# OMAPL-Extrention_Prototype.net
KiCad netlist of a schematic drawn in Altium Designer
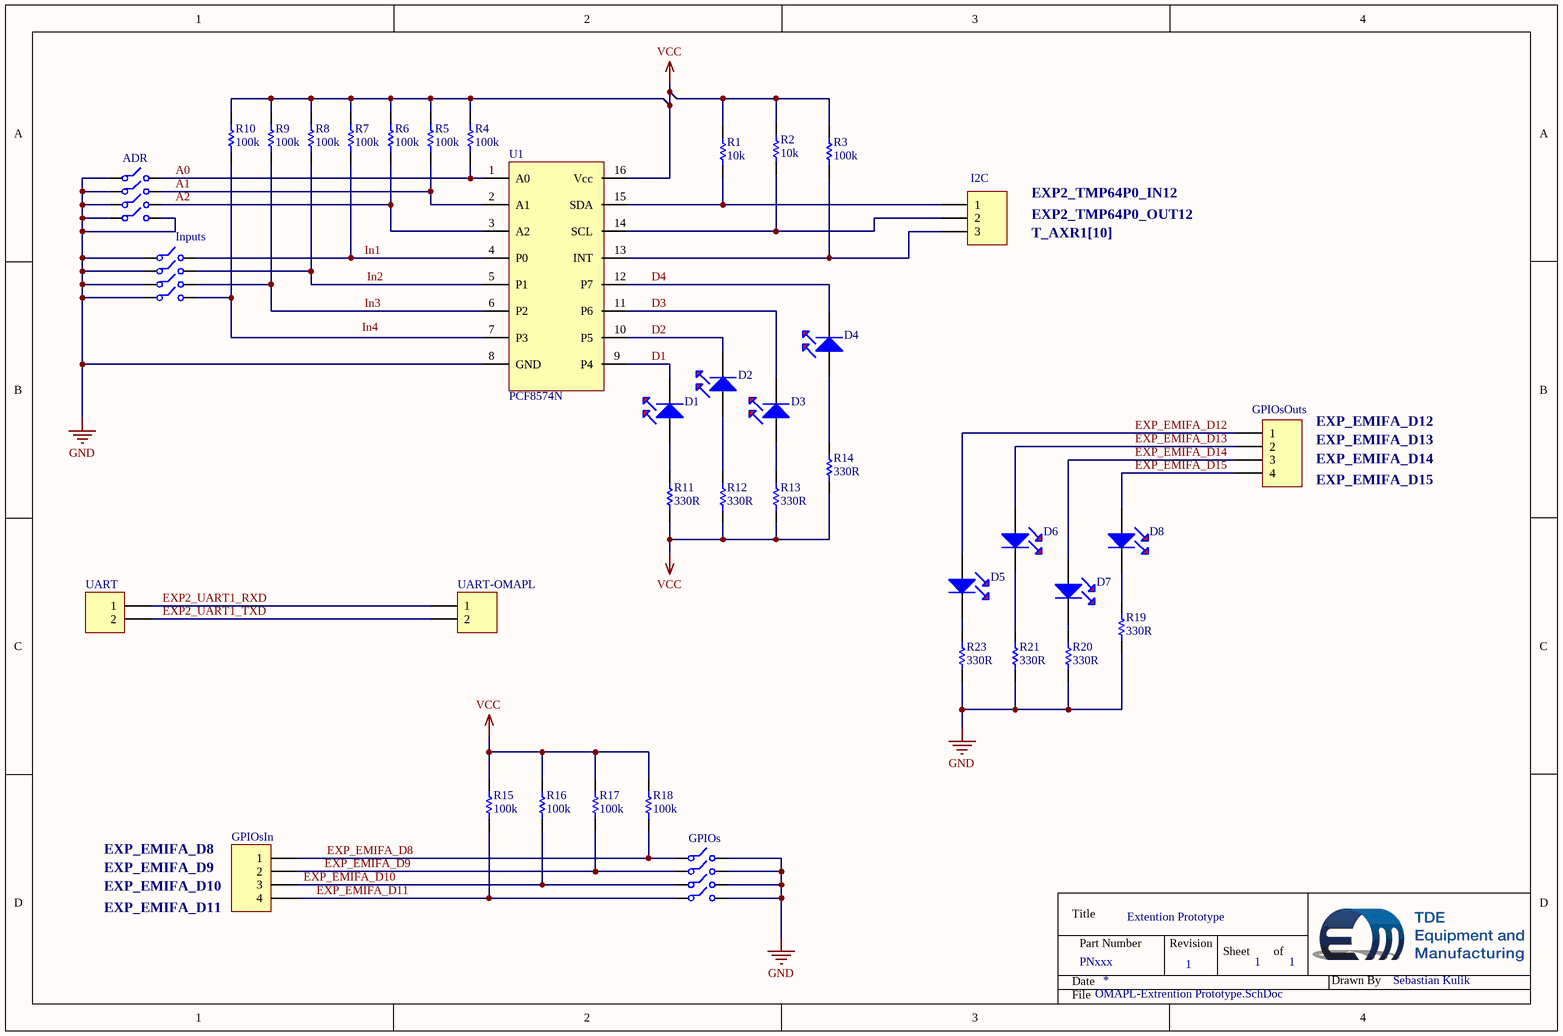
[diagram p0: OMAPL-Extrention Prototype.SchDoc]

(export (version "E")
  (design (tool "Eeschema 10.0.6"))
  (components
    (comp (ref "ADR")
      (value "WS-DITV-4DIP")
      (footprint "DIP-8-Ceramic-HT")
      (description "4 way DIP switch")
      (fields (field (name "MANUFACTURER") "WE") (field (name "PUBLISHER") "Sebastian Kulik"))
      (libsource (lib "Mechanical") (part "WS-DITV-4DIP"))
    )
    (comp (ref "D1")
      (value "151051RS11000")
      (footprint "LED2X5")
      (description "LED, 5mm, red, THT")
      (fields (field (name "MANUFACTURER") "WE") (field (name "PUBLISHER") "Sebastian Kulik"))
      (libsource (lib "Discrete") (part "151051RS11000"))
    )
    (comp (ref "D2")
      (value "151051RS11000")
      (footprint "LED2X5")
      (description "LED, 5mm, red, THT")
      (fields (field (name "MANUFACTURER") "WE") (field (name "PUBLISHER") "Sebastian Kulik"))
      (libsource (lib "Discrete") (part "151051RS11000"))
    )
    (comp (ref "D3")
      (value "151051RS11000")
      (footprint "LED2X5")
      (description "LED, 5mm, red, THT")
      (fields (field (name "MANUFACTURER") "WE") (field (name "PUBLISHER") "Sebastian Kulik"))
      (libsource (lib "Discrete") (part "151051RS11000"))
    )
    (comp (ref "D4")
      (value "151051RS11000")
      (footprint "LED2X5")
      (description "LED, 5mm, red, THT")
      (fields (field (name "MANUFACTURER") "WE") (field (name "PUBLISHER") "Sebastian Kulik"))
      (libsource (lib "Discrete") (part "151051RS11000"))
    )
    (comp (ref "D5")
      (value "151051RS11000")
      (footprint "LED2X5")
      (description "LED, 5mm, red, THT")
      (fields (field (name "MANUFACTURER") "WE") (field (name "PUBLISHER") "Sebastian Kulik"))
      (libsource (lib "Discrete") (part "151051RS11000"))
    )
    (comp (ref "D6")
      (value "151051RS11000")
      (footprint "LED2X5")
      (description "LED, 5mm, red, THT")
      (fields (field (name "MANUFACTURER") "WE") (field (name "PUBLISHER") "Sebastian Kulik"))
      (libsource (lib "Discrete") (part "151051RS11000"))
    )
    (comp (ref "D7")
      (value "151051RS11000")
      (footprint "LED2X5")
      (description "LED, 5mm, red, THT")
      (fields (field (name "MANUFACTURER") "WE") (field (name "PUBLISHER") "Sebastian Kulik"))
      (libsource (lib "Discrete") (part "151051RS11000"))
    )
    (comp (ref "D8")
      (value "151051RS11000")
      (footprint "LED2X5")
      (description "LED, 5mm, red, THT")
      (fields (field (name "MANUFACTURER") "WE") (field (name "PUBLISHER") "Sebastian Kulik"))
      (libsource (lib "Discrete") (part "151051RS11000"))
    )
    (comp (ref "GPIOs")
      (value "WS-DITV-4DIP")
      (footprint "DIP-8-Ceramic-HT")
      (description "4 way DIP switch")
      (fields (field (name "MANUFACTURER") "WE") (field (name "PUBLISHER") "Sebastian Kulik"))
      (libsource (lib "Mechanical") (part "WS-DITV-4DIP"))
    )
    (comp (ref "GPIOsIn")
      (value "Plug_4_90_2.54")
      (footprint "HDR1X4")
      (description "Plug, 4-Pin")
      (fields (field (name "MANUFACTURER") "WE") (field (name "PUBLISHER") "Sebastian Kulik"))
      (libsource (lib "") (part "Plug_4_90_2.54_1"))
    )
    (comp (ref "GPIOsOuts")
      (value "Plug_4_90_2.54")
      (footprint "HDR1X4")
      (description "Plug, 4-Pin")
      (fields (field (name "MANUFACTURER") "WE") (field (name "PUBLISHER") "Sebastian Kulik"))
      (libsource (lib "Connectors") (part "Plug_4_90_2.54"))
    )
    (comp (ref "I2C")
      (value "Plug_3_90_2.54")
      (footprint "HDR1X3")
      (description "Plug,-3-Pin")
      (fields (field (name "MANUFACTURER") "WE") (field (name "PUBLISHER") "Sebastian Kulik"))
      (libsource (lib "Connectors") (part "Plug_3_90_2.54"))
    )
    (comp (ref "Inputs")
      (value "WS-DITV-4DIP")
      (footprint "DIP-8-Ceramic-HT")
      (description "4 way DIP switch")
      (fields (field (name "MANUFACTURER") "WE") (field (name "PUBLISHER") "Sebastian Kulik"))
      (libsource (lib "Mechanical") (part "WS-DITV-4DIP"))
    )
    (comp (ref "R1")
      (value "10k")
      (footprint "Dummy-10mm")
      (description "Resistor-Dummy-THT")
      (fields (field (name "PUBLISHER") "Sebastian Kulik"))
      (libsource (lib "Resistors") (part "Resistor-Dummy-THT"))
    )
    (comp (ref "R2")
      (value "10k")
      (footprint "Dummy-10mm")
      (description "Resistor-Dummy-THT")
      (fields (field (name "PUBLISHER") "Sebastian Kulik"))
      (libsource (lib "Resistors") (part "Resistor-Dummy-THT"))
    )
    (comp (ref "R3")
      (value "100k")
      (footprint "Dummy-10mm")
      (description "Resistor-Dummy-THT")
      (fields (field (name "PUBLISHER") "Sebastian Kulik"))
      (libsource (lib "Resistors") (part "Resistor-Dummy-THT"))
    )
    (comp (ref "R4")
      (value "100k")
      (footprint "Dummy-10mm")
      (description "Resistor-Dummy-THT")
      (fields (field (name "PUBLISHER") "Sebastian Kulik"))
      (libsource (lib "Resistors") (part "Resistor-Dummy-THT"))
    )
    (comp (ref "R5")
      (value "100k")
      (footprint "Dummy-10mm")
      (description "Resistor-Dummy-THT")
      (fields (field (name "PUBLISHER") "Sebastian Kulik"))
      (libsource (lib "Resistors") (part "Resistor-Dummy-THT"))
    )
    (comp (ref "R6")
      (value "100k")
      (footprint "Dummy-10mm")
      (description "Resistor-Dummy-THT")
      (fields (field (name "PUBLISHER") "Sebastian Kulik"))
      (libsource (lib "Resistors") (part "Resistor-Dummy-THT"))
    )
    (comp (ref "R7")
      (value "100k")
      (footprint "Dummy-10mm")
      (description "Resistor-Dummy-THT")
      (fields (field (name "PUBLISHER") "Sebastian Kulik"))
      (libsource (lib "Resistors") (part "Resistor-Dummy-THT"))
    )
    (comp (ref "R8")
      (value "100k")
      (footprint "Dummy-10mm")
      (description "Resistor-Dummy-THT")
      (fields (field (name "PUBLISHER") "Sebastian Kulik"))
      (libsource (lib "Resistors") (part "Resistor-Dummy-THT"))
    )
    (comp (ref "R9")
      (value "100k")
      (footprint "Dummy-10mm")
      (description "Resistor-Dummy-THT")
      (fields (field (name "PUBLISHER") "Sebastian Kulik"))
      (libsource (lib "Resistors") (part "Resistor-Dummy-THT"))
    )
    (comp (ref "R10")
      (value "100k")
      (footprint "Dummy-10mm")
      (description "Resistor-Dummy-THT")
      (fields (field (name "PUBLISHER") "Sebastian Kulik"))
      (libsource (lib "Resistors") (part "Resistor-Dummy-THT"))
    )
    (comp (ref "R11")
      (value "330R")
      (footprint "Dummy-10mm")
      (description "Resistor-Dummy-THT")
      (fields (field (name "PUBLISHER") "Sebastian Kulik"))
      (libsource (lib "Resistors") (part "Resistor-Dummy-THT"))
    )
    (comp (ref "R12")
      (value "330R")
      (footprint "Dummy-10mm")
      (description "Resistor-Dummy-THT")
      (fields (field (name "PUBLISHER") "Sebastian Kulik"))
      (libsource (lib "Resistors") (part "Resistor-Dummy-THT"))
    )
    (comp (ref "R13")
      (value "330R")
      (footprint "Dummy-10mm")
      (description "Resistor-Dummy-THT")
      (fields (field (name "PUBLISHER") "Sebastian Kulik"))
      (libsource (lib "Resistors") (part "Resistor-Dummy-THT"))
    )
    (comp (ref "R14")
      (value "330R")
      (footprint "Dummy-10mm")
      (description "Resistor-Dummy-THT")
      (fields (field (name "PUBLISHER") "Sebastian Kulik"))
      (libsource (lib "Resistors") (part "Resistor-Dummy-THT"))
    )
    (comp (ref "R15")
      (value "100k")
      (footprint "Dummy-10mm")
      (description "Resistor-Dummy-THT")
      (fields (field (name "PUBLISHER") "Sebastian Kulik"))
      (libsource (lib "Resistors") (part "Resistor-Dummy-THT"))
    )
    (comp (ref "R16")
      (value "100k")
      (footprint "Dummy-10mm")
      (description "Resistor-Dummy-THT")
      (fields (field (name "PUBLISHER") "Sebastian Kulik"))
      (libsource (lib "Resistors") (part "Resistor-Dummy-THT"))
    )
    (comp (ref "R17")
      (value "100k")
      (footprint "Dummy-10mm")
      (description "Resistor-Dummy-THT")
      (fields (field (name "PUBLISHER") "Sebastian Kulik"))
      (libsource (lib "Resistors") (part "Resistor-Dummy-THT"))
    )
    (comp (ref "R18")
      (value "100k")
      (footprint "Dummy-10mm")
      (description "Resistor-Dummy-THT")
      (fields (field (name "PUBLISHER") "Sebastian Kulik"))
      (libsource (lib "Resistors") (part "Resistor-Dummy-THT"))
    )
    (comp (ref "R19")
      (value "330R")
      (footprint "Dummy-10mm")
      (description "Resistor-Dummy-THT")
      (fields (field (name "PUBLISHER") "Sebastian Kulik"))
      (libsource (lib "Resistors") (part "Resistor-Dummy-THT"))
    )
    (comp (ref "R20")
      (value "330R")
      (footprint "Dummy-10mm")
      (description "Resistor-Dummy-THT")
      (fields (field (name "PUBLISHER") "Sebastian Kulik"))
      (libsource (lib "Resistors") (part "Resistor-Dummy-THT"))
    )
    (comp (ref "R21")
      (value "330R")
      (footprint "Dummy-10mm")
      (description "Resistor-Dummy-THT")
      (fields (field (name "PUBLISHER") "Sebastian Kulik"))
      (libsource (lib "Resistors") (part "Resistor-Dummy-THT"))
    )
    (comp (ref "R23")
      (value "330R")
      (footprint "Dummy-10mm")
      (description "Resistor-Dummy-THT")
      (fields (field (name "PUBLISHER") "Sebastian Kulik"))
      (libsource (lib "Resistors") (part "Resistor-Dummy-THT"))
    )
    (comp (ref "U1")
      (value "PCF8574N")
      (footprint "DIP-16")
      (description "I2C 8-bit expander")
      (fields (field (name "MANUFACTURER") "TI") (field (name "PUBLISHER") "Sebastian Kulik"))
      (libsource (lib "ICs") (part "PCF8574N"))
    )
    (comp (ref "UART")
      (value "Plug_2_90_2.54")
      (footprint "HDR1X2")
      (description "Plug, 2-Pin")
      (fields (field (name "MANUFACTURER") "WE") (field (name "PUBLISHER") "Sebastian Kulik"))
      (libsource (lib "") (part "Plug_2_90_2.54_1"))
    )
    (comp (ref "UART-OMAPL")
      (value "Plug_2_90_2.54")
      (footprint "HDR1X2")
      (description "Plug, 2-Pin")
      (fields (field (name "MANUFACTURER") "WE") (field (name "PUBLISHER") "Sebastian Kulik"))
      (libsource (lib "Connectors") (part "Plug_2_90_2.54"))
    )
  )
  (nets
    (net (code "1") (name "/A0") (class "Default")
      (node (ref "ADR") (pin "8") (pinfunction "8_8") (pintype "passive"))
      (node (ref "R4") (pin "1") (pinfunction "1_1") (pintype "passive"))
      (node (ref "U1") (pin "1") (pinfunction "A0_1") (pintype "passive"))
    )
    (net (code "2") (name "/A1") (class "Default")
      (node (ref "ADR") (pin "7") (pinfunction "7_7") (pintype "passive"))
      (node (ref "R5") (pin "1") (pinfunction "1_1") (pintype "passive"))
      (node (ref "U1") (pin "2") (pinfunction "A1_2") (pintype "passive"))
    )
    (net (code "3") (name "/A2") (class "Default")
      (node (ref "ADR") (pin "6") (pinfunction "6_6") (pintype "passive"))
      (node (ref "R6") (pin "1") (pinfunction "1_1") (pintype "passive"))
      (node (ref "U1") (pin "3") (pinfunction "A2_3") (pintype "passive"))
    )
    (net (code "4") (name "/D1") (class "Default")
      (node (ref "D1") (pin "K") (pinfunction "K_K") (pintype "passive"))
      (node (ref "U1") (pin "9") (pinfunction "P4_9") (pintype "power_in"))
    )
    (net (code "5") (name "/D2") (class "Default")
      (node (ref "D2") (pin "K") (pinfunction "K_K") (pintype "passive"))
      (node (ref "U1") (pin "10") (pinfunction "P5_10") (pintype "power_in"))
    )
    (net (code "6") (name "/D3") (class "Default")
      (node (ref "D3") (pin "K") (pinfunction "K_K") (pintype "passive"))
      (node (ref "U1") (pin "11") (pinfunction "P6_11") (pintype "power_in"))
    )
    (net (code "7") (name "/D4") (class "Default")
      (node (ref "D4") (pin "K") (pinfunction "K_K") (pintype "passive"))
      (node (ref "U1") (pin "12") (pinfunction "P7_12") (pintype "power_in"))
    )
    (net (code "8") (name "/EXP2_UART1_RXD") (class "Default")
      (node (ref "UART") (pin "1") (pinfunction "1_1") (pintype "passive"))
      (node (ref "UART-OMAPL") (pin "1") (pinfunction "1_1") (pintype "passive"))
    )
    (net (code "9") (name "/EXP2_UART1_TXD") (class "Default")
      (node (ref "UART") (pin "2") (pinfunction "2_2") (pintype "passive"))
      (node (ref "UART-OMAPL") (pin "2") (pinfunction "2_2") (pintype "passive"))
    )
    (net (code "10") (name "/EXP_EMIFA_D8") (class "Default")
      (node (ref "GPIOs") (pin "1") (pinfunction "1_1") (pintype "passive"))
      (node (ref "GPIOsIn") (pin "1") (pinfunction "1_1") (pintype "passive"))
      (node (ref "R18") (pin "1") (pinfunction "1_1") (pintype "passive"))
    )
    (net (code "11") (name "/EXP_EMIFA_D9") (class "Default")
      (node (ref "GPIOs") (pin "2") (pinfunction "2_2") (pintype "passive"))
      (node (ref "GPIOsIn") (pin "2") (pinfunction "2_2") (pintype "passive"))
      (node (ref "R17") (pin "1") (pinfunction "1_1") (pintype "passive"))
    )
    (net (code "12") (name "/EXP_EMIFA_D10") (class "Default")
      (node (ref "GPIOs") (pin "3") (pinfunction "3_3") (pintype "passive"))
      (node (ref "GPIOsIn") (pin "3") (pinfunction "3_3") (pintype "passive"))
      (node (ref "R16") (pin "1") (pinfunction "1_1") (pintype "passive"))
    )
    (net (code "13") (name "/EXP_EMIFA_D11") (class "Default")
      (node (ref "GPIOs") (pin "4") (pinfunction "4_4") (pintype "passive"))
      (node (ref "GPIOsIn") (pin "4") (pinfunction "4_4") (pintype "passive"))
      (node (ref "R15") (pin "1") (pinfunction "1_1") (pintype "passive"))
    )
    (net (code "14") (name "/EXP_EMIFA_D12") (class "Default")
      (node (ref "D5") (pin "A") (pinfunction "A_A") (pintype "passive"))
      (node (ref "GPIOsOuts") (pin "1") (pinfunction "1_1") (pintype "passive"))
    )
    (net (code "15") (name "/EXP_EMIFA_D13") (class "Default")
      (node (ref "D6") (pin "A") (pinfunction "A_A") (pintype "passive"))
      (node (ref "GPIOsOuts") (pin "2") (pinfunction "2_2") (pintype "passive"))
    )
    (net (code "16") (name "/EXP_EMIFA_D14") (class "Default")
      (node (ref "D7") (pin "A") (pinfunction "A_A") (pintype "passive"))
      (node (ref "GPIOsOuts") (pin "3") (pinfunction "3_3") (pintype "passive"))
    )
    (net (code "17") (name "/EXP_EMIFA_D15") (class "Default")
      (node (ref "D8") (pin "A") (pinfunction "A_A") (pintype "passive"))
      (node (ref "GPIOsOuts") (pin "4") (pinfunction "4_4") (pintype "passive"))
    )
    (net (code "18") (name "/In1") (class "Default")
      (node (ref "Inputs") (pin "8") (pinfunction "8_8") (pintype "passive"))
      (node (ref "R7") (pin "1") (pinfunction "1_1") (pintype "passive"))
      (node (ref "U1") (pin "4") (pinfunction "P0_4") (pintype "passive"))
    )
    (net (code "19") (name "/In2") (class "Default")
      (node (ref "Inputs") (pin "7") (pinfunction "7_7") (pintype "passive"))
      (node (ref "R8") (pin "1") (pinfunction "1_1") (pintype "passive"))
      (node (ref "U1") (pin "5") (pinfunction "P1_5") (pintype "passive"))
    )
    (net (code "20") (name "/In3") (class "Default")
      (node (ref "Inputs") (pin "6") (pinfunction "6_6") (pintype "passive"))
      (node (ref "R9") (pin "1") (pinfunction "1_1") (pintype "passive"))
      (node (ref "U1") (pin "6") (pinfunction "P2_6") (pintype "passive"))
    )
    (net (code "22") (name "GND") (class "Default")
      (node (ref "ADR") (pin "1") (pinfunction "1_1") (pintype "passive"))
      (node (ref "ADR") (pin "2") (pinfunction "2_2") (pintype "passive"))
      (node (ref "ADR") (pin "3") (pinfunction "3_3") (pintype "passive"))
      (node (ref "ADR") (pin "4") (pinfunction "4_4") (pintype "passive"))
      (node (ref "ADR") (pin "5") (pinfunction "5_5") (pintype "passive"))
      (node (ref "GPIOs") (pin "5") (pinfunction "5_5") (pintype "passive"))
      (node (ref "GPIOs") (pin "6") (pinfunction "6_6") (pintype "passive"))
      (node (ref "GPIOs") (pin "7") (pinfunction "7_7") (pintype "passive"))
      (node (ref "GPIOs") (pin "8") (pinfunction "8_8") (pintype "passive"))
      (node (ref "Inputs") (pin "1") (pinfunction "1_1") (pintype "passive"))
      (node (ref "Inputs") (pin "2") (pinfunction "2_2") (pintype "passive"))
      (node (ref "Inputs") (pin "3") (pinfunction "3_3") (pintype "passive"))
      (node (ref "Inputs") (pin "4") (pinfunction "4_4") (pintype "passive"))
      (node (ref "R19") (pin "1") (pinfunction "1_1") (pintype "passive"))
      (node (ref "R20") (pin "1") (pinfunction "1_1") (pintype "passive"))
      (node (ref "R21") (pin "1") (pinfunction "1_1") (pintype "passive"))
      (node (ref "R23") (pin "1") (pinfunction "1_1") (pintype "passive"))
      (node (ref "U1") (pin "8") (pinfunction "GND_8") (pintype "power_in"))
    )
    (net (code "23") (name "Net-(D1-PadA)") (class "Default")
      (node (ref "D1") (pin "A") (pinfunction "A_A") (pintype "passive"))
      (node (ref "R11") (pin "2") (pinfunction "2_2") (pintype "passive"))
    )
    (net (code "24") (name "Net-(D2-PadA)") (class "Default")
      (node (ref "D2") (pin "A") (pinfunction "A_A") (pintype "passive"))
      (node (ref "R12") (pin "2") (pinfunction "2_2") (pintype "passive"))
    )
    (net (code "25") (name "Net-(D3-PadA)") (class "Default")
      (node (ref "D3") (pin "A") (pinfunction "A_A") (pintype "passive"))
      (node (ref "R13") (pin "2") (pinfunction "2_2") (pintype "passive"))
    )
    (net (code "26") (name "Net-(D4-PadA)") (class "Default")
      (node (ref "D4") (pin "A") (pinfunction "A_A") (pintype "passive"))
      (node (ref "R14") (pin "2") (pinfunction "2_2") (pintype "passive"))
    )
    (net (code "27") (name "Net-(D5-PadK)") (class "Default")
      (node (ref "D5") (pin "K") (pinfunction "K_K") (pintype "passive"))
      (node (ref "R23") (pin "2") (pinfunction "2_2") (pintype "passive"))
    )
    (net (code "28") (name "Net-(D6-PadK)") (class "Default")
      (node (ref "D6") (pin "K") (pinfunction "K_K") (pintype "passive"))
      (node (ref "R21") (pin "2") (pinfunction "2_2") (pintype "passive"))
    )
    (net (code "29") (name "Net-(D7-PadK)") (class "Default")
      (node (ref "D7") (pin "K") (pinfunction "K_K") (pintype "passive"))
      (node (ref "R20") (pin "2") (pinfunction "2_2") (pintype "passive"))
    )
    (net (code "30") (name "Net-(D8-PadK)") (class "Default")
      (node (ref "D8") (pin "K") (pinfunction "K_K") (pintype "passive"))
      (node (ref "R19") (pin "2") (pinfunction "2_2") (pintype "passive"))
    )
    (net (code "31") (name "Net-(U1-INT)") (class "Default")
      (node (ref "I2C") (pin "3") (pinfunction "3_3") (pintype "passive"))
      (node (ref "R3") (pin "1") (pinfunction "1_1") (pintype "passive"))
      (node (ref "U1") (pin "13") (pinfunction "INT_13") (pintype "passive"))
    )
    (net (code "32") (name "Net-(U1-P3)") (class "Default")
      (node (ref "Inputs") (pin "5") (pinfunction "5_5") (pintype "passive"))
      (node (ref "R10") (pin "1") (pinfunction "1_1") (pintype "passive"))
      (node (ref "U1") (pin "7") (pinfunction "P3_7") (pintype "passive"))
    )
    (net (code "33") (name "Net-(U1-SCL)") (class "Default")
      (node (ref "I2C") (pin "2") (pinfunction "2_2") (pintype "passive"))
      (node (ref "R2") (pin "1") (pinfunction "1_1") (pintype "passive"))
      (node (ref "U1") (pin "14") (pinfunction "SCL_14") (pintype "passive"))
    )
    (net (code "34") (name "Net-(U1-SDA)") (class "Default")
      (node (ref "I2C") (pin "1") (pinfunction "1_1") (pintype "passive"))
      (node (ref "R1") (pin "1") (pinfunction "1_1") (pintype "passive"))
      (node (ref "U1") (pin "15") (pinfunction "SDA_15") (pintype "power_in"))
    )
    (net (code "35") (name "VCC") (class "Default")
      (node (ref "R1") (pin "2") (pinfunction "2_2") (pintype "passive"))
      (node (ref "R10") (pin "2") (pinfunction "2_2") (pintype "passive"))
      (node (ref "R11") (pin "1") (pinfunction "1_1") (pintype "passive"))
      (node (ref "R12") (pin "1") (pinfunction "1_1") (pintype "passive"))
      (node (ref "R13") (pin "1") (pinfunction "1_1") (pintype "passive"))
      (node (ref "R14") (pin "1") (pinfunction "1_1") (pintype "passive"))
      (node (ref "R15") (pin "2") (pinfunction "2_2") (pintype "passive"))
      (node (ref "R16") (pin "2") (pinfunction "2_2") (pintype "passive"))
      (node (ref "R17") (pin "2") (pinfunction "2_2") (pintype "passive"))
      (node (ref "R18") (pin "2") (pinfunction "2_2") (pintype "passive"))
      (node (ref "R2") (pin "2") (pinfunction "2_2") (pintype "passive"))
      (node (ref "R3") (pin "2") (pinfunction "2_2") (pintype "passive"))
      (node (ref "R4") (pin "2") (pinfunction "2_2") (pintype "passive"))
      (node (ref "R5") (pin "2") (pinfunction "2_2") (pintype "passive"))
      (node (ref "R6") (pin "2") (pinfunction "2_2") (pintype "passive"))
      (node (ref "R7") (pin "2") (pinfunction "2_2") (pintype "passive"))
      (node (ref "R8") (pin "2") (pinfunction "2_2") (pintype "passive"))
      (node (ref "R9") (pin "2") (pinfunction "2_2") (pintype "passive"))
      (node (ref "U1") (pin "16") (pinfunction "Vcc_16") (pintype "passive"))
    )
  )
)
